# ArbPwrBoost_P44.net
KiCad netlist of a schematic drawn in Altium Designer
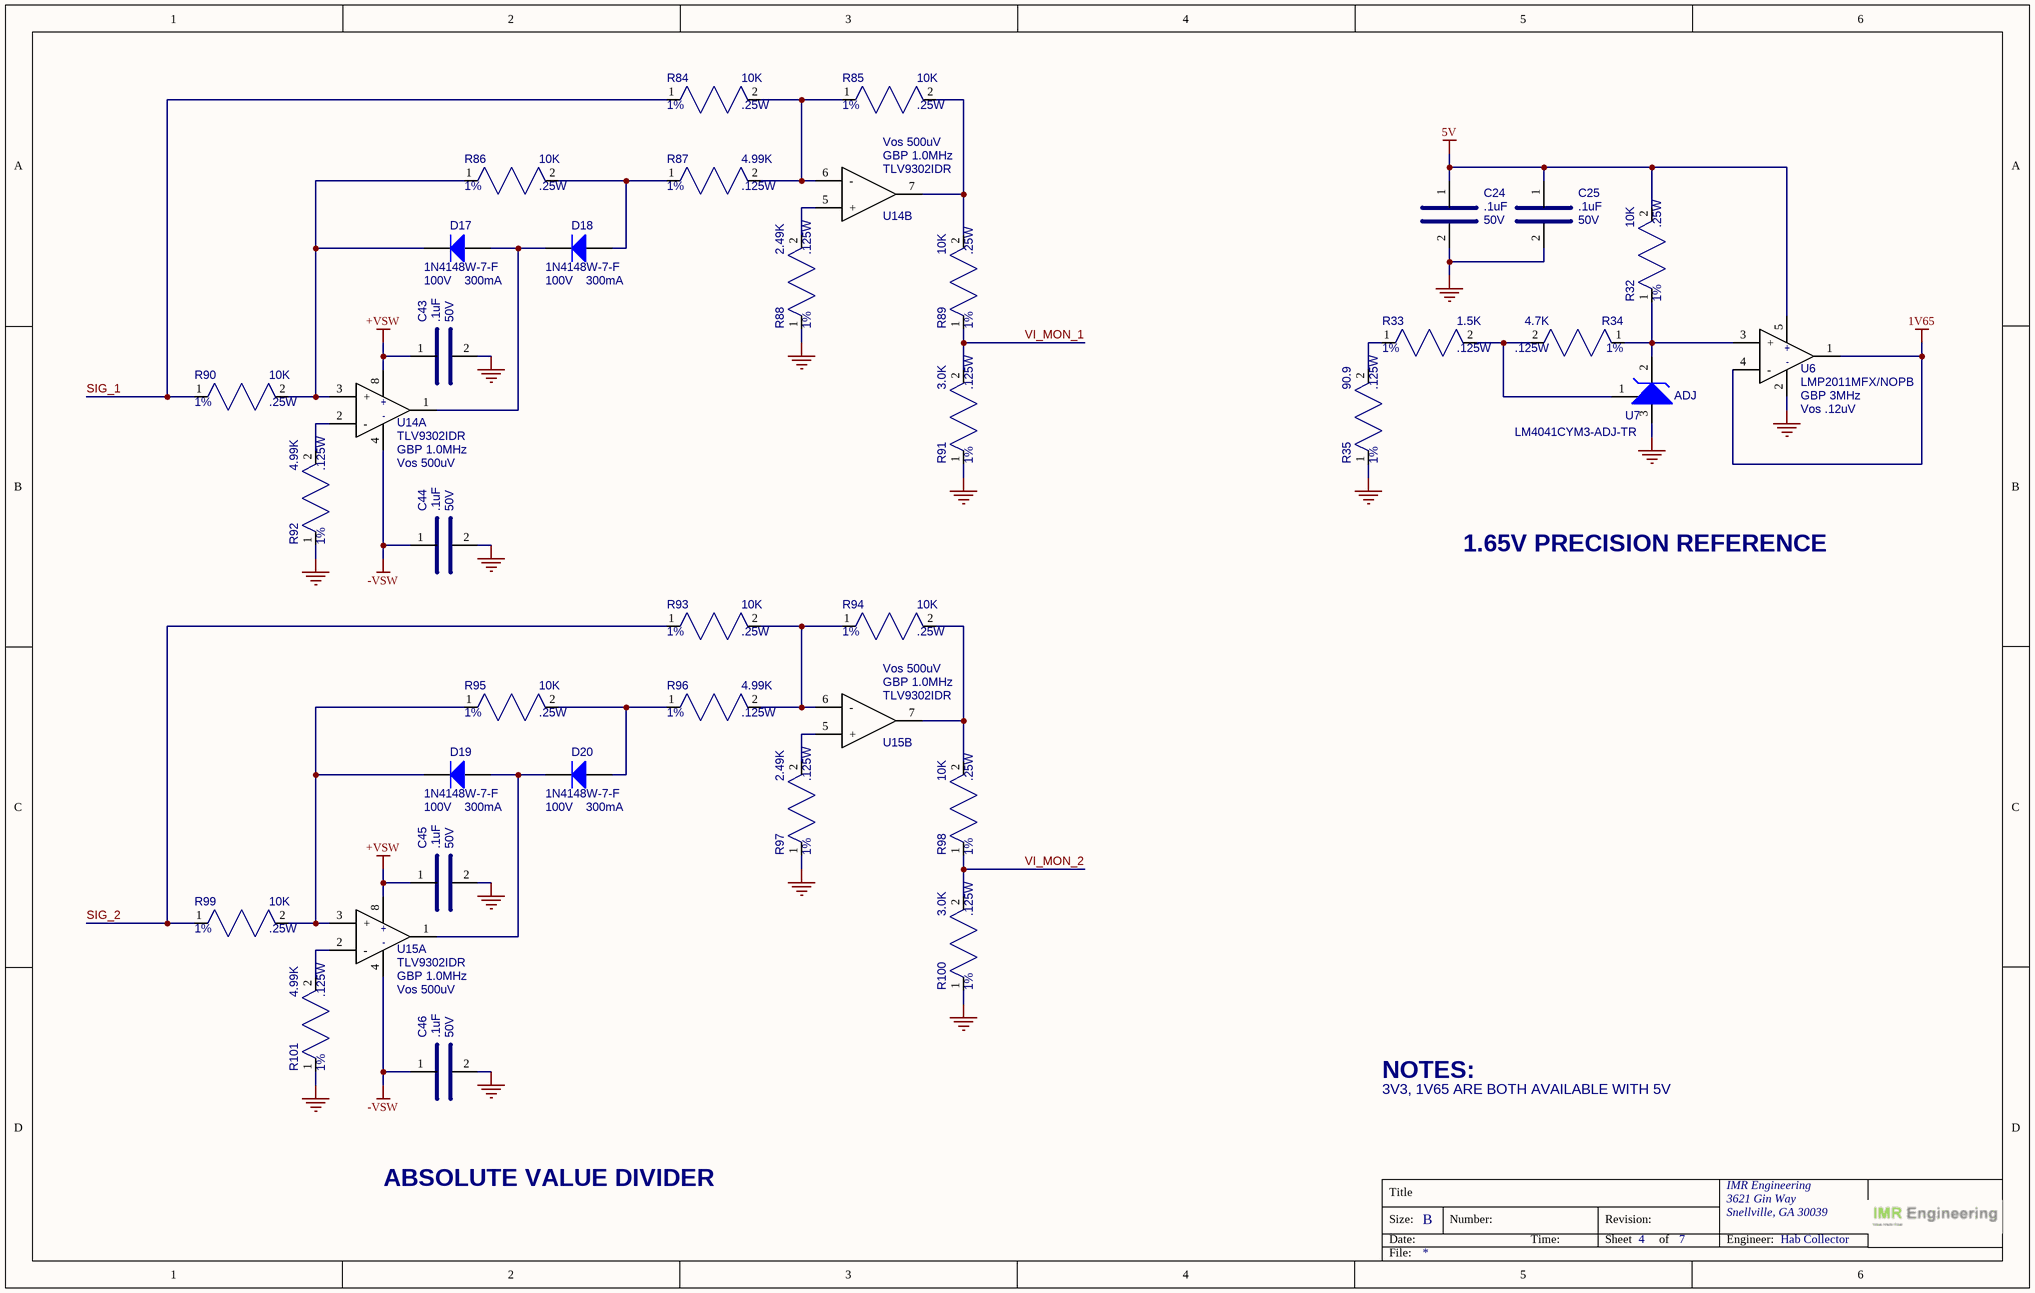
[diagram p0: ArbPwrBoost_P44.SchDoc]

(export (version "E")
  (design (tool "Eeschema 10.0.6"))
  (components
    (comp (ref "C24")
      (value ".1uF")
      (footprint "CAP_0805")
      (description "CAP CER 0.1UF 50V X7R 0805")
      (fields
        (field (name "MFG") "KYOCERA AVX")
        (field (name "VOLTAGE") "50V")
        (field (name "Comment") "KGM21NR71H104KT")
      )
      (libsource (lib "IMR_LIB_SCH_R2") (part "CAP_SMD_0.1UF_50V_0805"))
    )
    (comp (ref "C25")
      (value ".1uF")
      (footprint "CAP_0805")
      (description "CAP CER 0.1UF 50V X7R 0805")
      (fields
        (field (name "MFG") "KYOCERA AVX")
        (field (name "VOLTAGE") "50V")
        (field (name "Comment") "KGM21NR71H104KT")
      )
      (libsource (lib "IMR_LIB_SCH_R2") (part "CAP_SMD_0.1UF_50V_0805"))
    )
    (comp (ref "C43")
      (value ".1uF")
      (footprint "CAP_0805")
      (description "CAP CER 0.1UF 50V X7R 0805")
      (fields
        (field (name "MFG") "KYOCERA AVX")
        (field (name "VOLTAGE") "50V")
        (field (name "Comment") "KGM21NR71H104KT")
      )
      (libsource (lib "IMR_LIB_SCH_R2") (part "CAP_SMD_0.1UF_50V_0805"))
    )
    (comp (ref "C44")
      (value ".1uF")
      (footprint "CAP_0805")
      (description "CAP CER 0.1UF 50V X7R 0805")
      (fields
        (field (name "MFG") "KYOCERA AVX")
        (field (name "VOLTAGE") "50V")
        (field (name "Comment") "KGM21NR71H104KT")
      )
      (libsource (lib "IMR_LIB_SCH_R2") (part "CAP_SMD_0.1UF_50V_0805"))
    )
    (comp (ref "C45")
      (value ".1uF")
      (footprint "CAP_0805")
      (description "CAP CER 0.1UF 50V X7R 0805")
      (fields
        (field (name "MFG") "KYOCERA AVX")
        (field (name "VOLTAGE") "50V")
        (field (name "Comment") "KGM21NR71H104KT")
      )
      (libsource (lib "IMR_LIB_SCH_R2") (part "CAP_SMD_0.1UF_50V_0805"))
    )
    (comp (ref "C46")
      (value ".1uF")
      (footprint "CAP_0805")
      (description "CAP CER 0.1UF 50V X7R 0805")
      (fields
        (field (name "MFG") "KYOCERA AVX")
        (field (name "VOLTAGE") "50V")
        (field (name "Comment") "KGM21NR71H104KT")
      )
      (libsource (lib "IMR_LIB_SCH_R2") (part "CAP_SMD_0.1UF_50V_0805"))
    )
    (comp (ref "D17")
      (value "100V")
      (footprint "SOD123")
      (description "RELAY REED SPDT 250MA 5V")
      (fields
        (field (name "MFG") "Diodes Inc")
        (field (name "MFG_PN") "1N4148W-7-F")
        (field (name "CURRENT") "300mA")
        (field (name "Comment") "1N4148W-7-F")
      )
      (libsource (lib "IMR_LIB_SCH_R2") (part "DIODE_1N4148W-7-F"))
    )
    (comp (ref "D18")
      (value "100V")
      (footprint "SOD123")
      (description "RELAY REED SPDT 250MA 5V")
      (fields
        (field (name "MFG") "Diodes Inc")
        (field (name "MFG_PN") "1N4148W-7-F")
        (field (name "CURRENT") "300mA")
        (field (name "Comment") "1N4148W-7-F")
      )
      (libsource (lib "IMR_LIB_SCH_R2") (part "DIODE_1N4148W-7-F"))
    )
    (comp (ref "D19")
      (value "100V")
      (footprint "SOD123")
      (description "RELAY REED SPDT 250MA 5V")
      (fields
        (field (name "MFG") "Diodes Inc")
        (field (name "MFG_PN") "1N4148W-7-F")
        (field (name "CURRENT") "300mA")
        (field (name "Comment") "1N4148W-7-F")
      )
      (libsource (lib "IMR_LIB_SCH_R2") (part "DIODE_1N4148W-7-F"))
    )
    (comp (ref "D20")
      (value "100V")
      (footprint "SOD123")
      (description "RELAY REED SPDT 250MA 5V")
      (fields
        (field (name "MFG") "Diodes Inc")
        (field (name "MFG_PN") "1N4148W-7-F")
        (field (name "CURRENT") "300mA")
        (field (name "Comment") "1N4148W-7-F")
      )
      (libsource (lib "IMR_LIB_SCH_R2") (part "DIODE_1N4148W-7-F"))
    )
    (comp (ref "R32")
      (value "10K")
      (footprint "RES_0805")
      (description "RES SMD 10K OHM 1% 1/4W 0805")
      (fields
        (field (name "MFG") "Yageo")
        (field (name "POWER") ".25W")
        (field (name "TOLERANCE") "1%")
        (field (name "Comment") "RC0805FR-7W10KL")
      )
      (libsource (lib "IMR_LIB_SCH_R2") (part "RES_SMD_10K_0805_1/4W_1%"))
    )
    (comp (ref "R33")
      (value "1.5K")
      (footprint "RES_0805")
      (description "RES SMD 1.5K OHM 1% 1/8W 0805")
      (fields
        (field (name "MFG") "Yageo")
        (field (name "POWER") ".125W")
        (field (name "TOLERANCE") "1%")
        (field (name "Comment") "RC0805FR-071K5L")
      )
      (libsource (lib "IMR_LIB_SCH_R2") (part "RES_SMD_1.5K_0805_1/8W_1%"))
    )
    (comp (ref "R34")
      (value "4.7K")
      (footprint "RES_0805")
      (description "RES SMD 4.7K OHM 1% 1/8W 0805")
      (fields
        (field (name "MFG") "Yageo")
        (field (name "POWER") ".125W")
        (field (name "TOLERANCE") "1%")
        (field (name "Comment") "RC0805FR-134K7L")
      )
      (libsource (lib "IMR_LIB_SCH_R2") (part "RES_SMD_4.7K_0805_1/8W_1%"))
    )
    (comp (ref "R35")
      (value "90.9")
      (footprint "RES_0805")
      (description "RES SMD 90.9 OHM 1% 1/8W 0805")
      (fields
        (field (name "MFG") "Yageo")
        (field (name "POWER") ".125W")
        (field (name "TOLERANCE") "1%")
        (field (name "Comment") "RC0805FR-0790R9L")
      )
      (libsource (lib "IMR_LIB_SCH_R2") (part "RES_SMD_90.9_0805_1/8W_1%"))
    )
    (comp (ref "R84")
      (value "10K")
      (footprint "RES_0805")
      (description "RES SMD 10K OHM 1% 1/4W 0805")
      (fields
        (field (name "MFG") "Yageo")
        (field (name "POWER") ".25W")
        (field (name "TOLERANCE") "1%")
        (field (name "Comment") "RC0805FR-7W10KL")
      )
      (libsource (lib "IMR_LIB_SCH_R2") (part "RES_SMD_10K_0805_1/4W_1%"))
    )
    (comp (ref "R85")
      (value "10K")
      (footprint "RES_0805")
      (description "RES SMD 10K OHM 1% 1/4W 0805")
      (fields
        (field (name "MFG") "Yageo")
        (field (name "POWER") ".25W")
        (field (name "TOLERANCE") "1%")
        (field (name "Comment") "RC0805FR-7W10KL")
      )
      (libsource (lib "IMR_LIB_SCH_R2") (part "RES_SMD_10K_0805_1/4W_1%"))
    )
    (comp (ref "R86")
      (value "10K")
      (footprint "RES_0805")
      (description "RES SMD 10K OHM 1% 1/4W 0805")
      (fields
        (field (name "MFG") "Yageo")
        (field (name "POWER") ".25W")
        (field (name "TOLERANCE") "1%")
        (field (name "Comment") "RC0805FR-7W10KL")
      )
      (libsource (lib "IMR_LIB_SCH_R2") (part "RES_SMD_10K_0805_1/4W_1%"))
    )
    (comp (ref "R87")
      (value "4.99K")
      (footprint "RES_0805")
      (description "RES SMD 4.99K OHM 1% 1/8W 0805")
      (fields
        (field (name "MFG") "Yageo")
        (field (name "POWER") ".125W")
        (field (name "TOLERANCE") "1%")
        (field (name "Comment") "RC0805FR-134K99L")
      )
      (libsource (lib "IMR_LIB_SCH_R2") (part "RES_SMD_4.99K_0805_1/8W_1%"))
    )
    (comp (ref "R88")
      (value "2.49K")
      (footprint "RES_0805")
      (description "RES SMD 2.49K OHM 1% 1/8W 0805")
      (fields
        (field (name "MFG") "Yageo")
        (field (name "POWER") ".125W")
        (field (name "TOLERANCE") "1%")
        (field (name "Comment") "RC0805FR-132K49L")
      )
      (libsource (lib "IMR_LIB_SCH_R2") (part "RES_SMD_2.49K_0805_1/8W_1%"))
    )
    (comp (ref "R89")
      (value "10K")
      (footprint "RES_0805")
      (description "RES SMD 10K OHM 1% 1/4W 0805")
      (fields
        (field (name "MFG") "Yageo")
        (field (name "POWER") ".25W")
        (field (name "TOLERANCE") "1%")
        (field (name "Comment") "RC0805FR-7W10KL")
      )
      (libsource (lib "IMR_LIB_SCH_R2") (part "RES_SMD_10K_0805_1/4W_1%"))
    )
    (comp (ref "R90")
      (value "10K")
      (footprint "RES_0805")
      (description "RES SMD 10K OHM 1% 1/4W 0805")
      (fields
        (field (name "MFG") "Yageo")
        (field (name "POWER") ".25W")
        (field (name "TOLERANCE") "1%")
        (field (name "Comment") "RC0805FR-7W10KL")
      )
      (libsource (lib "IMR_LIB_SCH_R2") (part "RES_SMD_10K_0805_1/4W_1%"))
    )
    (comp (ref "R91")
      (value "3.0K")
      (footprint "RES_0805")
      (description "RES SMD 3.0K OHM 1% 1/8W 0805")
      (fields
        (field (name "MFG") "Yageo")
        (field (name "POWER") ".125W")
        (field (name "TOLERANCE") "1%")
        (field (name "Comment") "RC0805FR-133KL")
      )
      (libsource (lib "IMR_LIB_SCH_R2") (part "RES_SMD_3.0K_0805_1/8W_1%"))
    )
    (comp (ref "R92")
      (value "4.99K")
      (footprint "RES_0805")
      (description "RES SMD 4.99K OHM 1% 1/8W 0805")
      (fields
        (field (name "MFG") "Yageo")
        (field (name "POWER") ".125W")
        (field (name "TOLERANCE") "1%")
        (field (name "Comment") "RC0805FR-134K99L")
      )
      (libsource (lib "IMR_LIB_SCH_R2") (part "RES_SMD_4.99K_0805_1/8W_1%"))
    )
    (comp (ref "R93")
      (value "10K")
      (footprint "RES_0805")
      (description "RES SMD 10K OHM 1% 1/4W 0805")
      (fields
        (field (name "MFG") "Yageo")
        (field (name "POWER") ".25W")
        (field (name "TOLERANCE") "1%")
        (field (name "Comment") "RC0805FR-7W10KL")
      )
      (libsource (lib "IMR_LIB_SCH_R2") (part "RES_SMD_10K_0805_1/4W_1%"))
    )
    (comp (ref "R94")
      (value "10K")
      (footprint "RES_0805")
      (description "RES SMD 10K OHM 1% 1/4W 0805")
      (fields
        (field (name "MFG") "Yageo")
        (field (name "POWER") ".25W")
        (field (name "TOLERANCE") "1%")
        (field (name "Comment") "RC0805FR-7W10KL")
      )
      (libsource (lib "IMR_LIB_SCH_R2") (part "RES_SMD_10K_0805_1/4W_1%"))
    )
    (comp (ref "R95")
      (value "10K")
      (footprint "RES_0805")
      (description "RES SMD 10K OHM 1% 1/4W 0805")
      (fields
        (field (name "MFG") "Yageo")
        (field (name "POWER") ".25W")
        (field (name "TOLERANCE") "1%")
        (field (name "Comment") "RC0805FR-7W10KL")
      )
      (libsource (lib "IMR_LIB_SCH_R2") (part "RES_SMD_10K_0805_1/4W_1%"))
    )
    (comp (ref "R96")
      (value "4.99K")
      (footprint "RES_0805")
      (description "RES SMD 4.99K OHM 1% 1/8W 0805")
      (fields
        (field (name "MFG") "Yageo")
        (field (name "POWER") ".125W")
        (field (name "TOLERANCE") "1%")
        (field (name "Comment") "RC0805FR-134K99L")
      )
      (libsource (lib "IMR_LIB_SCH_R2") (part "RES_SMD_4.99K_0805_1/8W_1%"))
    )
    (comp (ref "R97")
      (value "2.49K")
      (footprint "RES_0805")
      (description "RES SMD 2.49K OHM 1% 1/8W 0805")
      (fields
        (field (name "MFG") "Yageo")
        (field (name "POWER") ".125W")
        (field (name "TOLERANCE") "1%")
        (field (name "Comment") "RC0805FR-132K49L")
      )
      (libsource (lib "IMR_LIB_SCH_R2") (part "RES_SMD_2.49K_0805_1/8W_1%"))
    )
    (comp (ref "R98")
      (value "10K")
      (footprint "RES_0805")
      (description "RES SMD 10K OHM 1% 1/4W 0805")
      (fields
        (field (name "MFG") "Yageo")
        (field (name "POWER") ".25W")
        (field (name "TOLERANCE") "1%")
        (field (name "Comment") "RC0805FR-7W10KL")
      )
      (libsource (lib "IMR_LIB_SCH_R2") (part "RES_SMD_10K_0805_1/4W_1%"))
    )
    (comp (ref "R99")
      (value "10K")
      (footprint "RES_0805")
      (description "RES SMD 10K OHM 1% 1/4W 0805")
      (fields
        (field (name "MFG") "Yageo")
        (field (name "POWER") ".25W")
        (field (name "TOLERANCE") "1%")
        (field (name "Comment") "RC0805FR-7W10KL")
      )
      (libsource (lib "IMR_LIB_SCH_R2") (part "RES_SMD_10K_0805_1/4W_1%"))
    )
    (comp (ref "R100")
      (value "3.0K")
      (footprint "RES_0805")
      (description "RES SMD 3.0K OHM 1% 1/8W 0805")
      (fields
        (field (name "MFG") "Yageo")
        (field (name "POWER") ".125W")
        (field (name "TOLERANCE") "1%")
        (field (name "Comment") "RC0805FR-133KL")
      )
      (libsource (lib "IMR_LIB_SCH_R2") (part "RES_SMD_3.0K_0805_1/8W_1%"))
    )
    (comp (ref "R101")
      (value "4.99K")
      (footprint "RES_0805")
      (description "RES SMD 4.99K OHM 1% 1/8W 0805")
      (fields
        (field (name "MFG") "Yageo")
        (field (name "POWER") ".125W")
        (field (name "TOLERANCE") "1%")
        (field (name "Comment") "RC0805FR-134K99L")
      )
      (libsource (lib "IMR_LIB_SCH_R2") (part "RES_SMD_4.99K_0805_1/8W_1%"))
    )
    (comp (ref "U6")
      (value "GBP 3MHz")
      (footprint "SOT-23-5")
      (description "IC OPAMP GP 3MHZ .12uV CIRCUIT SOT23-5")
      (fields
        (field (name "MFG") "Texas Instruments")
        (field (name "MFG_PN") "LMP2011MFX/NOPB")
        (field (name "VOS") "Vos .12uV")
        (field (name "Comment") "LMP2011MFX/NOPB")
      )
      (libsource (lib "IMR_LIB_SCH_R2") (part "OPAMP_LMP2011MFX/NOPB"))
    )
    (comp (ref "U7")
      (value "ADJ")
      (footprint "SOT-23")
      (description "IC VREF SHUNT ADJ 0.5% SOT23-3")
      (fields
        (field (name "MFG") "Microchip")
        (field (name "MFG_PN") "LM4041CYM3-ADJ-TR")
        (field (name "Comment") "LM4041CYM3-ADJ-TR")
      )
      (libsource (lib "IMR_LIB_SCH_R2") (part "IC_LM4041CYM3-ADJ-TR"))
    )
    (comp (ref "U14")
      (value "GBP 1.0MHz")
      (footprint "SOIC-8_49")
      (description "IC OPAMP GP 2 CIRCUIT 8SOIC")
      (fields
        (field (name "MFG") "Texas Instruments")
        (field (name "MFG_PN") "TLV9302IDR")
        (field (name "VOS") "Vos 500uV")
        (field (name "Comment") "TLV9302IDR")
      )
      (libsource (lib "IMR_LIB_SCH_R2") (part "OPAMP_TLV9302IDR"))
    )
    (comp (ref "U15")
      (value "GBP 1.0MHz")
      (footprint "SOIC-8_49")
      (description "IC OPAMP GP 2 CIRCUIT 8SOIC")
      (fields
        (field (name "MFG") "Texas Instruments")
        (field (name "MFG_PN") "TLV9302IDR")
        (field (name "VOS") "Vos 500uV")
        (field (name "Comment") "TLV9302IDR")
      )
      (libsource (lib "IMR_LIB_SCH_R2") (part "OPAMP_TLV9302IDR"))
    )
  )
  (nets
    (net (code "1") (name "+VSW") (class "Default")
      (node (ref "C43") (pin "1") (pinfunction "1_1") (pintype "passive"))
      (node (ref "C45") (pin "1") (pinfunction "1_1") (pintype "passive"))
      (node (ref "U14") (pin "8") (pintype "passive"))
      (node (ref "U15") (pin "8") (pintype "passive"))
    )
    (net (code "2") (name "-VSW") (class "Default")
      (node (ref "C44") (pin "1") (pinfunction "1_1") (pintype "passive"))
      (node (ref "C46") (pin "1") (pinfunction "1_1") (pintype "passive"))
      (node (ref "U14") (pin "4") (pintype "passive"))
      (node (ref "U15") (pin "4") (pintype "passive"))
    )
    (net (code "3") (name "/SIG_1") (class "Default")
      (node (ref "R84") (pin "1") (pinfunction "1_1") (pintype "passive"))
      (node (ref "R90") (pin "1") (pinfunction "1_1") (pintype "passive"))
    )
    (net (code "4") (name "/SIG_2") (class "Default")
      (node (ref "R93") (pin "1") (pinfunction "1_1") (pintype "passive"))
      (node (ref "R99") (pin "1") (pinfunction "1_1") (pintype "passive"))
    )
    (net (code "5") (name "/VI_MON_1") (class "Default")
      (node (ref "R89") (pin "1") (pinfunction "1_1") (pintype "passive"))
      (node (ref "R91") (pin "2") (pinfunction "2_2") (pintype "passive"))
    )
    (net (code "6") (name "/VI_MON_2") (class "Default")
      (node (ref "R100") (pin "2") (pinfunction "2_2") (pintype "passive"))
      (node (ref "R98") (pin "1") (pinfunction "1_1") (pintype "passive"))
    )
    (net (code "7") (name "1V65") (class "Default")
      (node (ref "U6") (pin "1") (pintype "passive"))
      (node (ref "U6") (pin "4") (pinfunction "-_4") (pintype "passive"))
    )
    (net (code "8") (name "5V") (class "Default")
      (node (ref "C24") (pin "1") (pinfunction "1_1") (pintype "passive"))
      (node (ref "C25") (pin "1") (pinfunction "1_1") (pintype "passive"))
      (node (ref "R32") (pin "2") (pinfunction "2_2") (pintype "passive"))
      (node (ref "U6") (pin "5") (pintype "passive"))
    )
    (net (code "9") (name "GND") (class "Default")
      (node (ref "C24") (pin "2") (pinfunction "2_2") (pintype "passive"))
      (node (ref "C25") (pin "2") (pinfunction "2_2") (pintype "passive"))
      (node (ref "C43") (pin "2") (pinfunction "2_2") (pintype "passive"))
      (node (ref "C44") (pin "2") (pinfunction "2_2") (pintype "passive"))
      (node (ref "C45") (pin "2") (pinfunction "2_2") (pintype "passive"))
      (node (ref "C46") (pin "2") (pinfunction "2_2") (pintype "passive"))
      (node (ref "R100") (pin "1") (pinfunction "1_1") (pintype "passive"))
      (node (ref "R101") (pin "1") (pinfunction "1_1") (pintype "passive"))
      (node (ref "R35") (pin "1") (pinfunction "1_1") (pintype "passive"))
      (node (ref "R88") (pin "1") (pinfunction "1_1") (pintype "passive"))
      (node (ref "R91") (pin "1") (pinfunction "1_1") (pintype "passive"))
      (node (ref "R92") (pin "1") (pinfunction "1_1") (pintype "passive"))
      (node (ref "R97") (pin "1") (pinfunction "1_1") (pintype "passive"))
      (node (ref "U6") (pin "2") (pintype "passive"))
      (node (ref "U7") (pin "3") (pinfunction "A_3") (pintype "passive"))
    )
    (net (code "10") (name "Net-(D17-A)") (class "Default")
      (node (ref "D17") (pin "1") (pinfunction "A_1") (pintype "passive"))
      (node (ref "D18") (pin "2") (pinfunction "K_2") (pintype "passive"))
      (node (ref "U14") (pin "1") (pintype "passive"))
    )
    (net (code "11") (name "Net-(D17-K)") (class "Default")
      (node (ref "D17") (pin "2") (pinfunction "K_2") (pintype "passive"))
      (node (ref "R86") (pin "1") (pinfunction "1_1") (pintype "passive"))
      (node (ref "R90") (pin "2") (pinfunction "2_2") (pintype "passive"))
      (node (ref "U14") (pin "3") (pinfunction "+_3") (pintype "passive"))
    )
    (net (code "12") (name "Net-(D18-A)") (class "Default")
      (node (ref "D18") (pin "1") (pinfunction "A_1") (pintype "passive"))
      (node (ref "R86") (pin "2") (pinfunction "2_2") (pintype "passive"))
      (node (ref "R87") (pin "1") (pinfunction "1_1") (pintype "passive"))
    )
    (net (code "13") (name "Net-(D19-A)") (class "Default")
      (node (ref "D19") (pin "1") (pinfunction "A_1") (pintype "passive"))
      (node (ref "D20") (pin "2") (pinfunction "K_2") (pintype "passive"))
      (node (ref "U15") (pin "1") (pintype "passive"))
    )
    (net (code "14") (name "Net-(D19-K)") (class "Default")
      (node (ref "D19") (pin "2") (pinfunction "K_2") (pintype "passive"))
      (node (ref "R95") (pin "1") (pinfunction "1_1") (pintype "passive"))
      (node (ref "R99") (pin "2") (pinfunction "2_2") (pintype "passive"))
      (node (ref "U15") (pin "3") (pinfunction "+_3") (pintype "passive"))
    )
    (net (code "15") (name "Net-(D20-A)") (class "Default")
      (node (ref "D20") (pin "1") (pinfunction "A_1") (pintype "passive"))
      (node (ref "R95") (pin "2") (pinfunction "2_2") (pintype "passive"))
      (node (ref "R96") (pin "1") (pinfunction "1_1") (pintype "passive"))
    )
    (net (code "16") (name "Net-(R33-Pad1)") (class "Default")
      (node (ref "R33") (pin "1") (pinfunction "1_1") (pintype "passive"))
      (node (ref "R35") (pin "2") (pinfunction "2_2") (pintype "passive"))
    )
    (net (code "17") (name "Net-(R85-Pad2)") (class "Default")
      (node (ref "R85") (pin "2") (pinfunction "2_2") (pintype "passive"))
      (node (ref "R89") (pin "2") (pinfunction "2_2") (pintype "passive"))
      (node (ref "U14") (pin "7") (pintype "passive"))
    )
    (net (code "18") (name "Net-(R94-Pad2)") (class "Default")
      (node (ref "R94") (pin "2") (pinfunction "2_2") (pintype "passive"))
      (node (ref "R98") (pin "2") (pinfunction "2_2") (pintype "passive"))
      (node (ref "U15") (pin "7") (pintype "passive"))
    )
    (net (code "19") (name "Net-(U6-+)") (class "Default")
      (node (ref "R32") (pin "1") (pinfunction "1_1") (pintype "passive"))
      (node (ref "R34") (pin "1") (pinfunction "1_1") (pintype "passive"))
      (node (ref "U6") (pin "3") (pinfunction "+_3") (pintype "passive"))
      (node (ref "U7") (pin "2") (pinfunction "K_2") (pintype "passive"))
    )
    (net (code "20") (name "Net-(U7-FB)") (class "Default")
      (node (ref "R33") (pin "2") (pinfunction "2_2") (pintype "passive"))
      (node (ref "R34") (pin "2") (pinfunction "2_2") (pintype "passive"))
      (node (ref "U7") (pin "1") (pinfunction "FB_1") (pintype "passive"))
    )
    (net (code "21") (name "Net-(U14A--)") (class "Default")
      (node (ref "R92") (pin "2") (pinfunction "2_2") (pintype "passive"))
      (node (ref "U14") (pin "2") (pinfunction "-_2") (pintype "passive"))
    )
    (net (code "22") (name "Net-(U14B-+)") (class "Default")
      (node (ref "R88") (pin "2") (pinfunction "2_2") (pintype "passive"))
      (node (ref "U14") (pin "5") (pinfunction "+_5") (pintype "passive"))
    )
    (net (code "23") (name "Net-(U14B--)") (class "Default")
      (node (ref "R84") (pin "2") (pinfunction "2_2") (pintype "passive"))
      (node (ref "R85") (pin "1") (pinfunction "1_1") (pintype "passive"))
      (node (ref "R87") (pin "2") (pinfunction "2_2") (pintype "passive"))
      (node (ref "U14") (pin "6") (pinfunction "-_6") (pintype "passive"))
    )
    (net (code "24") (name "Net-(U15A--)") (class "Default")
      (node (ref "R101") (pin "2") (pinfunction "2_2") (pintype "passive"))
      (node (ref "U15") (pin "2") (pinfunction "-_2") (pintype "passive"))
    )
    (net (code "25") (name "Net-(U15B-+)") (class "Default")
      (node (ref "R97") (pin "2") (pinfunction "2_2") (pintype "passive"))
      (node (ref "U15") (pin "5") (pinfunction "+_5") (pintype "passive"))
    )
    (net (code "26") (name "Net-(U15B--)") (class "Default")
      (node (ref "R93") (pin "2") (pinfunction "2_2") (pintype "passive"))
      (node (ref "R94") (pin "1") (pinfunction "1_1") (pintype "passive"))
      (node (ref "R96") (pin "2") (pinfunction "2_2") (pintype "passive"))
      (node (ref "U15") (pin "6") (pinfunction "-_6") (pintype "passive"))
    )
  )
)
